# USBcircuit.net
KiCad netlist of a schematic drawn in EAGLE
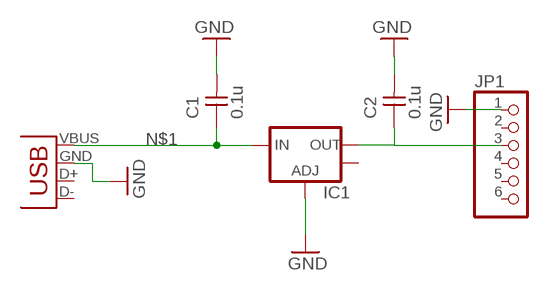
[diagram p0: schematic, sheet 1]

(export (version "E")
  (design (tool "Eeschema 10.0.6"))
  (components
    (comp (ref "C1")
      (value "0.1u")
      (footprint "eagle-import:1608")
      (libsource (lib "eagle-import") (part "1608"))
    )
    (comp (ref "C2")
      (value "0.1u")
      (footprint "eagle-import:1608")
      (libsource (lib "eagle-import") (part "1608"))
    )
    (comp (ref "IC1")
      (value "V_REG_LM1117SOT223")
      (footprint "eagle-import:SOT223")
      (libsource (lib "eagle-import") (part "V_REG_LM1117SOT223"))
    )
    (comp (ref "JP1")
      (value "PINHD-1X6NORMAL")
      (footprint "eagle-import:1X06")
      (libsource (lib "eagle-import") (part "PINHD-1X6NORMAL"))
    )
    (comp (ref "JP3")
      (value "USB-A-H")
      (footprint "eagle-import:USB-A-H")
      (libsource (lib "eagle-import") (part "USB-A-H"))
    )
  )
  (nets
    (net (code "1") (name "/N$1") (class "Default")
      (node (ref "C1") (pin "P$1") (pinfunction "1_P$1") (pintype "passive"))
      (node (ref "IC1") (pin "3") (pinfunction "IN_3") (pintype "input"))
      (node (ref "JP3") (pin "VBUS") (pinfunction "GND_VBUS") (pintype "bidirectional"))
    )
    (net (code "2") (name "GND") (class "Default")
      (node (ref "C1") (pin "P$2") (pinfunction "2_P$2") (pintype "passive"))
      (node (ref "C2") (pin "P$2") (pinfunction "2_P$2") (pintype "passive"))
      (node (ref "IC1") (pin "1") (pinfunction "ADJ_1") (pintype "input"))
      (node (ref "JP1") (pin "1") (pinfunction "1_1") (pintype "passive"))
      (node (ref "JP3") (pin "GND") (pinfunction "VBUS_GND") (pintype "bidirectional"))
    )
    (net (code "3") (name "Net-(C2-1)") (class "Default")
      (node (ref "C2") (pin "P$1") (pinfunction "1_P$1") (pintype "passive"))
      (node (ref "IC1") (pin "2") (pinfunction "OUT_2") (pintype "output"))
      (node (ref "JP1") (pin "3") (pinfunction "3_3") (pintype "passive"))
    )
    (net (code "4") (name "unconnected-(IC1-OUT-Pad4)") (class "Default")
      (node (ref "IC1") (pin "4") (pinfunction "OUT_4") (pintype "output"))
    )
    (net (code "5") (name "unconnected-(JP1-Pad2)") (class "Default")
      (node (ref "JP1") (pin "2") (pinfunction "2_2") (pintype "passive"))
    )
    (net (code "6") (name "unconnected-(JP1-Pad4)") (class "Default")
      (node (ref "JP1") (pin "4") (pinfunction "4_4") (pintype "passive"))
    )
    (net (code "7") (name "unconnected-(JP1-Pad5)") (class "Default")
      (node (ref "JP1") (pin "5") (pinfunction "5_5") (pintype "passive"))
    )
    (net (code "8") (name "unconnected-(JP1-Pad6)") (class "Default")
      (node (ref "JP1") (pin "6") (pinfunction "6_6") (pintype "passive"))
    )
    (net (code "9") (name "unconnected-(JP3-D+-PadD-)") (class "Default")
      (node (ref "JP3") (pin "D-") (pinfunction "D+_D-") (pintype "bidirectional"))
    )
    (net (code "10") (name "unconnected-(JP3-D--PadD+)") (class "Default")
      (node (ref "JP3") (pin "D+") (pinfunction "D-_D+") (pintype "bidirectional"))
    )
  )
)
